# Power_Switching_Circuit_rev3.net
KiCad netlist of a schematic drawn in EAGLE
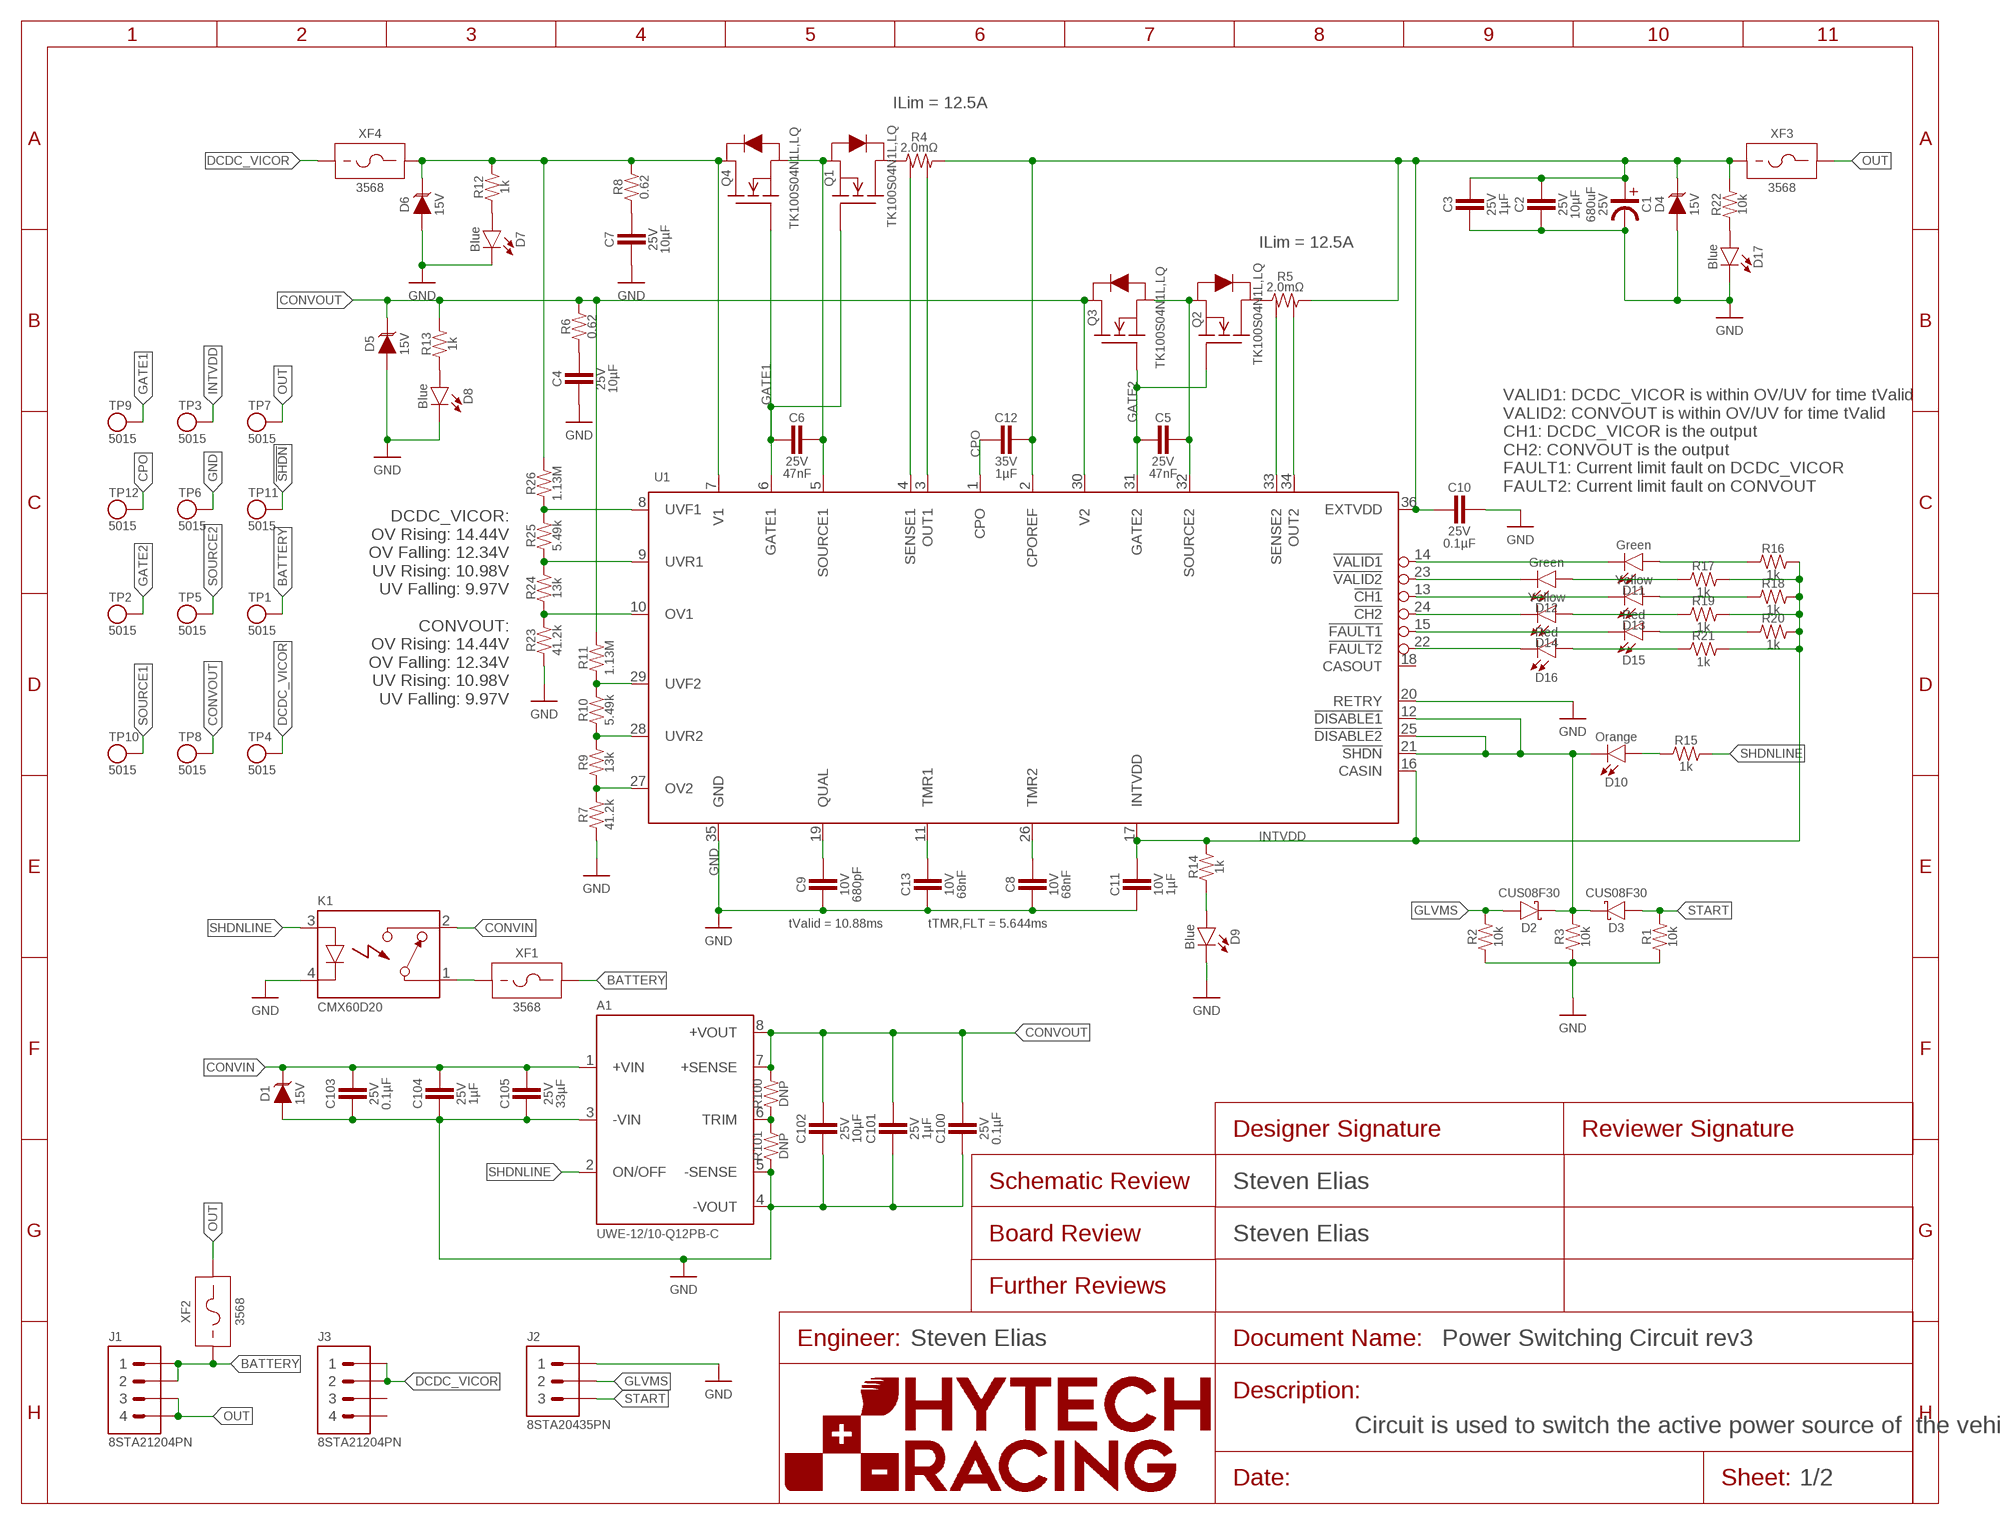
[diagram p0: schematic, sheet 1]
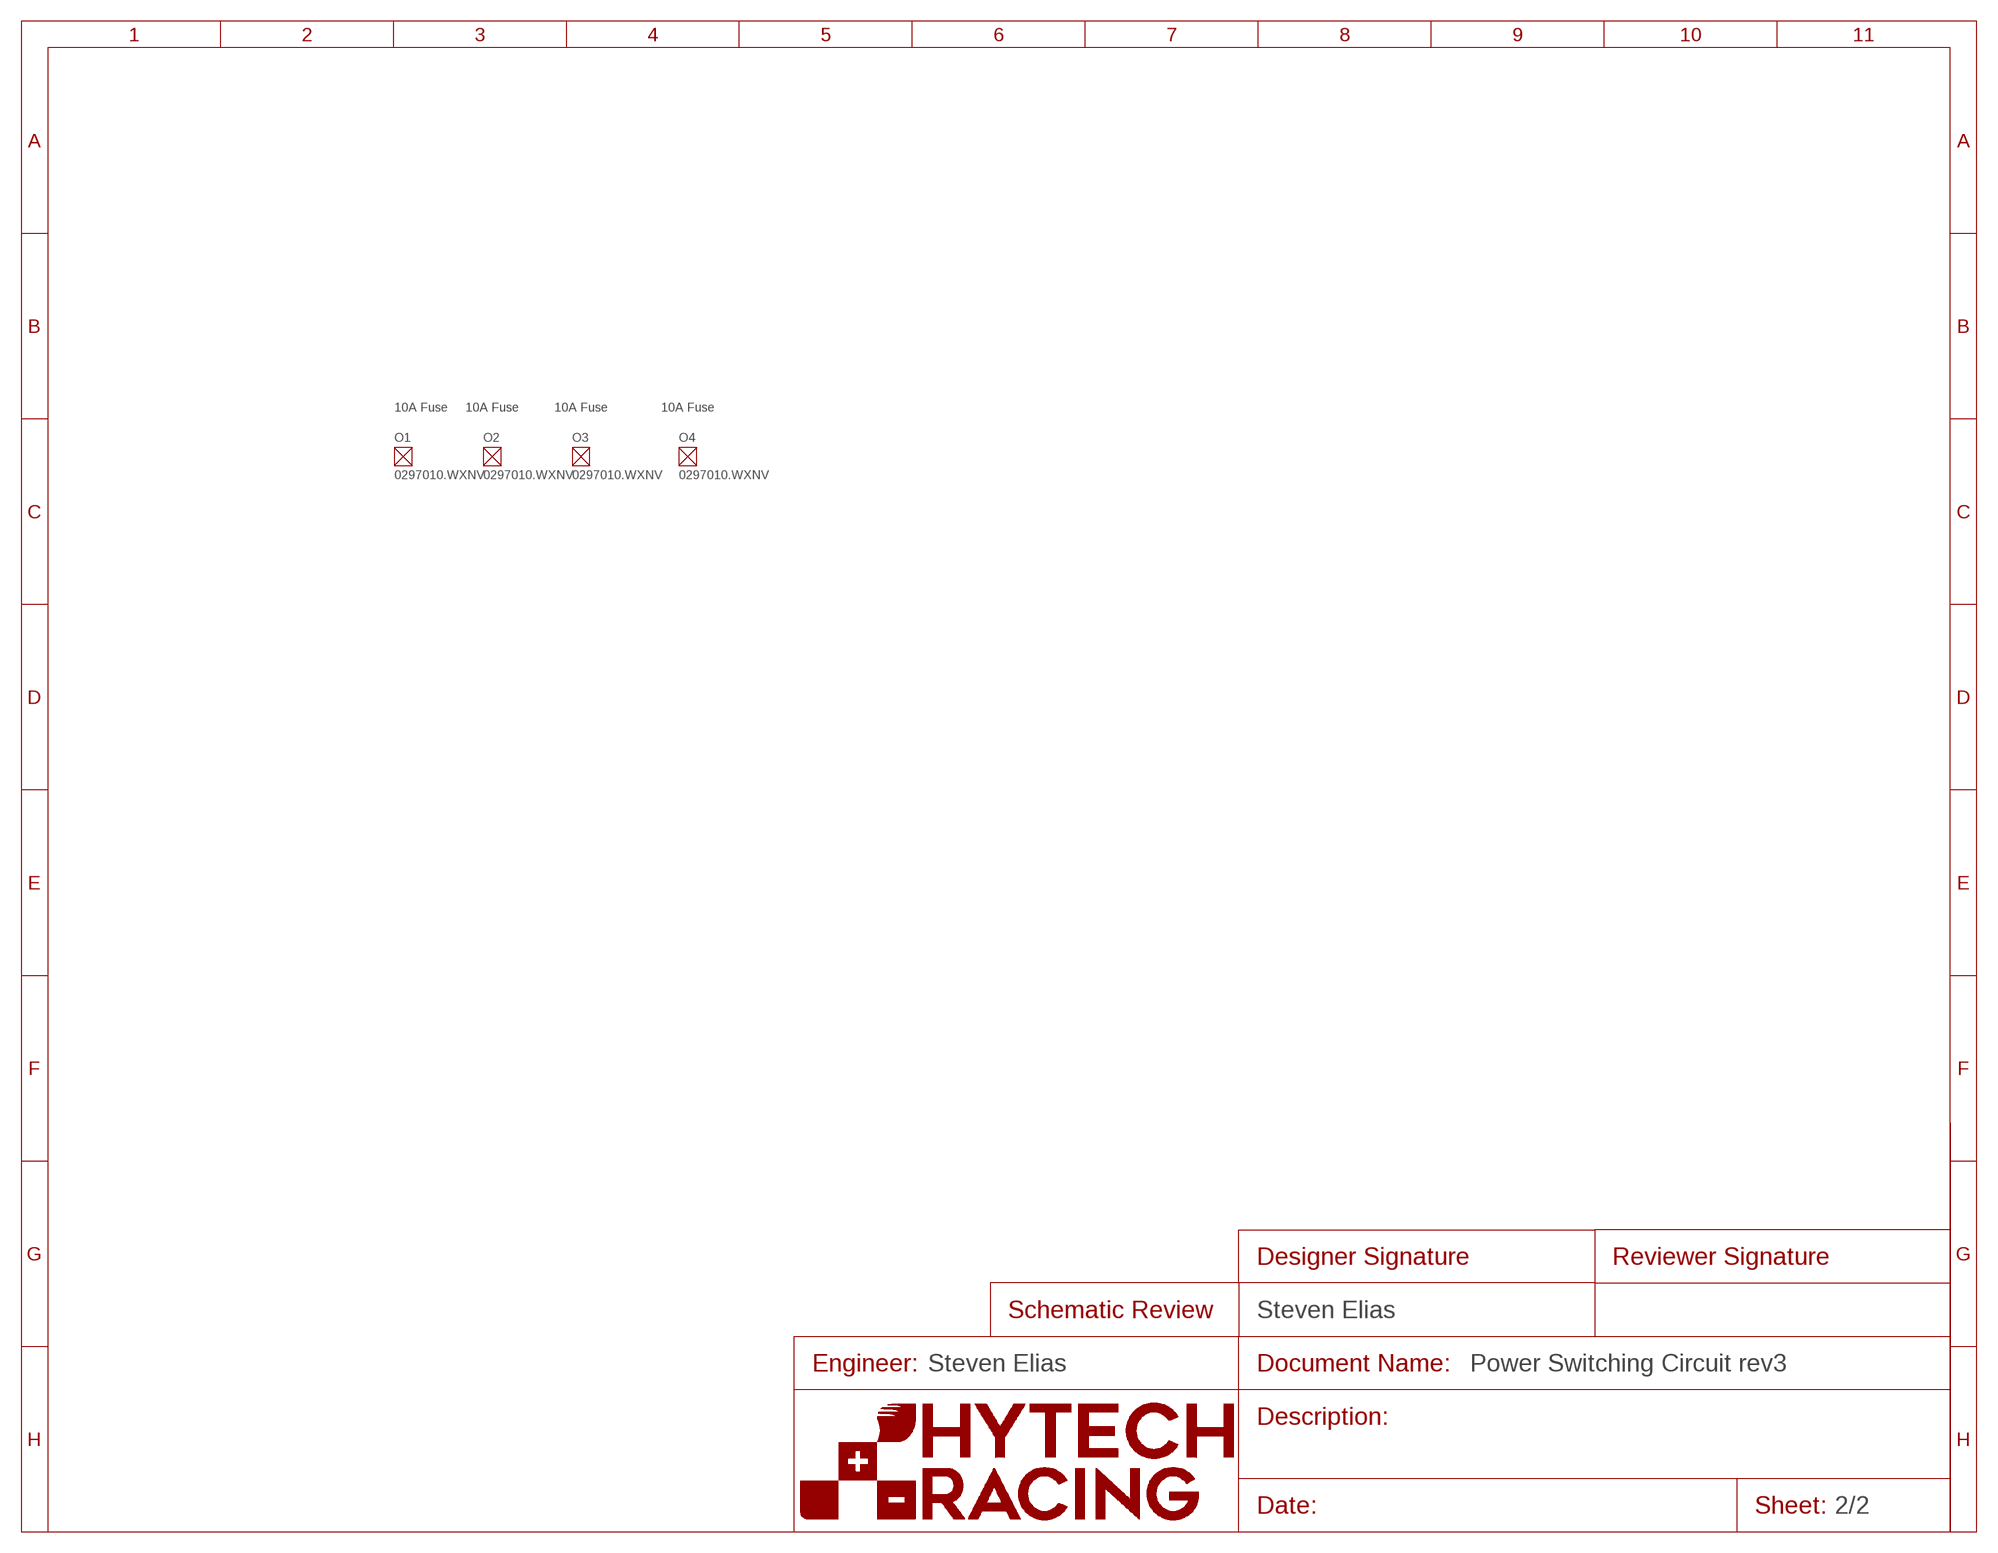
[diagram p1: schematic, sheet 2]

(export (version "E")
  (design (tool "Eeschema 10.0.6"))
  (components
    (comp (ref "A1")
      (value "UWE-12/10-Q12PB-C")
      (footprint "eagle-import:UWE-_")
      (fields
        (field (name "MANUFACTURER") "Murata Power Solutions Inc.")
        (field (name "MPN") "UWE-12/10-Q12PB-C")
      )
      (libsource (lib "eagle-import") (part "UWE-12/10-Q12PB-C"))
    )
    (comp (ref "C1")
      (value "EEUFP1E681")
      (footprint "eagle-import:EEUFP1E_")
      (fields
        (field (name "CAPACITANCE") "680uF")
        (field (name "MANUFACTURER") "Panasonic Electronic Components")
        (field (name "MPN") "EEU-FP1E681")
        (field (name "TOLERANCE") "20%")
        (field (name "VOLTAGE") "25V")
      )
      (libsource (lib "eagle-import") (part "EEUFP1E681"))
    )
    (comp (ref "C2")
      (value "CAPACITOR_0603_25V_10UF")
      (footprint "eagle-import:0603-CAP")
      (fields
        (field (name "CAPACITANCE") "10µF")
        (field (name "MANUFACTURER") "Murata Electronics")
        (field (name "MPN") "GRM188R61E106MA73D")
        (field (name "TOLERANCE") "20%")
        (field (name "VOLTAGE") "25V")
      )
      (libsource (lib "eagle-import") (part "CAPACITOR_?_060325V_10UF"))
    )
    (comp (ref "C3")
      (value "CAPACITOR_0603_25V_1UF")
      (footprint "eagle-import:0603-CAP")
      (fields
        (field (name "CAPACITANCE") "1µF")
        (field (name "MANUFACTURER") "Samsung Electro-Mechanics")
        (field (name "MPN") "CL10B105KA8NNNC")
        (field (name "TOLERANCE") "10%")
        (field (name "VOLTAGE") "25V")
      )
      (libsource (lib "eagle-import") (part "CAPACITOR_?_060325V_1UF"))
    )
    (comp (ref "C4")
      (value "CAPACITOR_0603_25V_10UF")
      (footprint "eagle-import:0603-CAP")
      (fields
        (field (name "CAPACITANCE") "10µF")
        (field (name "MANUFACTURER") "Murata Electronics")
        (field (name "MPN") "GRM188R61E106MA73D")
        (field (name "TOLERANCE") "20%")
        (field (name "VOLTAGE") "25V")
      )
      (libsource (lib "eagle-import") (part "CAPACITOR_?_060325V_10UF"))
    )
    (comp (ref "C5")
      (value "CAPACITOR_0603_25V_47NF")
      (footprint "eagle-import:0603-CAP")
      (fields
        (field (name "CAPACITANCE") "47nF")
        (field (name "MANUFACTURER") "Kyocera AVX")
        (field (name "MPN") "06033C473K4Z2A")
        (field (name "TOLERANCE") "10%")
        (field (name "VOLTAGE") "25V")
      )
      (libsource (lib "eagle-import") (part "CAPACITOR_?_060325V_47NF"))
    )
    (comp (ref "C6")
      (value "CAPACITOR_0603_25V_47NF")
      (footprint "eagle-import:0603-CAP")
      (fields
        (field (name "CAPACITANCE") "47nF")
        (field (name "MANUFACTURER") "Kyocera AVX")
        (field (name "MPN") "06033C473K4Z2A")
        (field (name "TOLERANCE") "10%")
        (field (name "VOLTAGE") "25V")
      )
      (libsource (lib "eagle-import") (part "CAPACITOR_?_060325V_47NF"))
    )
    (comp (ref "C7")
      (value "CAPACITOR_0603_25V_10UF")
      (footprint "eagle-import:0603-CAP")
      (fields
        (field (name "CAPACITANCE") "10µF")
        (field (name "MANUFACTURER") "Murata Electronics")
        (field (name "MPN") "GRM188R61E106MA73D")
        (field (name "TOLERANCE") "20%")
        (field (name "VOLTAGE") "25V")
      )
      (libsource (lib "eagle-import") (part "CAPACITOR_?_060325V_10UF"))
    )
    (comp (ref "C8")
      (value "CAPACITOR_0603_10V_68NF")
      (footprint "eagle-import:0603-CAP")
      (fields
        (field (name "CAPACITANCE") "68nF")
        (field (name "MANUFACTURER") "KEMET")
        (field (name "MPN") "C0603C683K8RACTU")
        (field (name "TOLERANCE") "10%")
        (field (name "VOLTAGE") "10V")
      )
      (libsource (lib "eagle-import") (part "CAPACITOR_?_060310V_68NF"))
    )
    (comp (ref "C9")
      (value "CAPACITOR_0603_10V_680PF")
      (footprint "eagle-import:0603-CAP")
      (fields
        (field (name "CAPACITANCE") "680pF")
        (field (name "MANUFACTURER") "Würth Elektronik")
        (field (name "MPN") "885012006013")
        (field (name "TOLERANCE") "5%")
        (field (name "VOLTAGE") "10V")
      )
      (libsource (lib "eagle-import") (part "CAPACITOR_?_060310V_680PF"))
    )
    (comp (ref "C10")
      (value "CAPACITOR_0603_25V_0.1UF")
      (footprint "eagle-import:0603-CAP")
      (fields
        (field (name "CAPACITANCE") "0.1µF")
        (field (name "MANUFACTURER") "Samsung Electro-Mechanics")
        (field (name "MPN") "CL10B104KA8NNNC")
        (field (name "TOLERANCE") "10%")
        (field (name "VOLTAGE") "25V")
      )
      (libsource (lib "eagle-import") (part "CAPACITOR_?_060325V_0.1UF"))
    )
    (comp (ref "C11")
      (value "CAPACITOR_0603_10V_1UF")
      (footprint "eagle-import:0603-CAP")
      (fields
        (field (name "CAPACITANCE") "1µF")
        (field (name "MANUFACTURER") "Yageo")
        (field (name "MPN") "CC0603KRX7R6BB105")
        (field (name "TOLERANCE") "10%")
        (field (name "VOLTAGE") "10V")
      )
      (libsource (lib "eagle-import") (part "CAPACITOR_?_060310V_1UF"))
    )
    (comp (ref "C12")
      (value "CAPACITOR_0603_35V_1UF")
      (footprint "eagle-import:0603-CAP")
      (fields
        (field (name "CAPACITANCE") "1µF")
        (field (name "MANUFACTURER") "TDK Corporation")
        (field (name "MPN") "C1608X7R1V105K080AE")
        (field (name "TOLERANCE") "10%")
        (field (name "VOLTAGE") "35V")
      )
      (libsource (lib "eagle-import") (part "CAPACITOR_?_060335V_1UF"))
    )
    (comp (ref "C13")
      (value "CAPACITOR_0603_10V_68NF")
      (footprint "eagle-import:0603-CAP")
      (fields
        (field (name "CAPACITANCE") "68nF")
        (field (name "MANUFACTURER") "KEMET")
        (field (name "MPN") "C0603C683K8RACTU")
        (field (name "TOLERANCE") "10%")
        (field (name "VOLTAGE") "10V")
      )
      (libsource (lib "eagle-import") (part "CAPACITOR_?_060310V_68NF"))
    )
    (comp (ref "C100")
      (value "CAPACITOR_0603_25V_0.1UF")
      (footprint "eagle-import:0603-CAP")
      (fields
        (field (name "CAPACITANCE") "0.1µF")
        (field (name "MANUFACTURER") "Samsung Electro-Mechanics")
        (field (name "MPN") "CL10B104KA8NNNC")
        (field (name "TOLERANCE") "10%")
        (field (name "VOLTAGE") "25V")
      )
      (libsource (lib "eagle-import") (part "CAPACITOR_?_060325V_0.1UF"))
    )
    (comp (ref "C101")
      (value "CAPACITOR_0603_25V_1UF")
      (footprint "eagle-import:0603-CAP")
      (fields
        (field (name "CAPACITANCE") "1µF")
        (field (name "MANUFACTURER") "Samsung Electro-Mechanics")
        (field (name "MPN") "CL10B105KA8NNNC")
        (field (name "TOLERANCE") "10%")
        (field (name "VOLTAGE") "25V")
      )
      (libsource (lib "eagle-import") (part "CAPACITOR_?_060325V_1UF"))
    )
    (comp (ref "C102")
      (value "CAPACITOR_0603_25V_10UF")
      (footprint "eagle-import:0603-CAP")
      (fields
        (field (name "CAPACITANCE") "10µF")
        (field (name "MANUFACTURER") "Murata Electronics")
        (field (name "MPN") "GRM188R61E106MA73D")
        (field (name "TOLERANCE") "20%")
        (field (name "VOLTAGE") "25V")
      )
      (libsource (lib "eagle-import") (part "CAPACITOR_?_060325V_10UF"))
    )
    (comp (ref "C103")
      (value "CAPACITOR_0603_25V_0.1UF")
      (footprint "eagle-import:0603-CAP")
      (fields
        (field (name "CAPACITANCE") "0.1µF")
        (field (name "MANUFACTURER") "Samsung Electro-Mechanics")
        (field (name "MPN") "CL10B104KA8NNNC")
        (field (name "TOLERANCE") "10%")
        (field (name "VOLTAGE") "25V")
      )
      (libsource (lib "eagle-import") (part "CAPACITOR_?_060325V_0.1UF"))
    )
    (comp (ref "C104")
      (value "CAPACITOR_0603_25V_1UF")
      (footprint "eagle-import:0603-CAP")
      (fields
        (field (name "CAPACITANCE") "1µF")
        (field (name "MANUFACTURER") "Samsung Electro-Mechanics")
        (field (name "MPN") "CL10B105KA8NNNC")
        (field (name "TOLERANCE") "10%")
        (field (name "VOLTAGE") "25V")
      )
      (libsource (lib "eagle-import") (part "CAPACITOR_?_060325V_1UF"))
    )
    (comp (ref "C105")
      (value "CAPACITOR_1206_25V_33UF")
      (footprint "eagle-import:1206-CAP")
      (fields
        (field (name "CAPACITANCE") "33µF")
        (field (name "MANUFACTURER") "TDK Corporation")
        (field (name "MPN") "C3216X5R1E336M160AC")
        (field (name "TOLERANCE") "20%")
        (field (name "VOLTAGE") "25V")
      )
      (libsource (lib "eagle-import") (part "CAPACITOR_?_120625V_33UF"))
    )
    (comp (ref "D1")
      (value "TVS_15V")
      (footprint "eagle-import:SOT-23")
      (fields
        (field (name "MANUFACTURER") "Vishay General Semiconductor - Diodes Division")
        (field (name "MPN") "GSOT15-E3-08")
        (field (name "VOLTAGE") "15V")
      )
      (libsource (lib "eagle-import") (part "TVS_15V"))
    )
    (comp (ref "D2")
      (value "SCHOTTKY_SOD323_30V")
      (footprint "eagle-import:SOD-323")
      (fields
        (field (name "MANUFACTURER") "Toshiba Semiconductor and Storage")
        (field (name "MPN") "CUS08F30")
        (field (name "VOLTAGE") "30V")
      )
      (libsource (lib "eagle-import") (part "SCHOTTKY_?_SOD32330V"))
    )
    (comp (ref "D3")
      (value "SCHOTTKY_SOD323_30V")
      (footprint "eagle-import:SOD-323")
      (fields
        (field (name "MANUFACTURER") "Toshiba Semiconductor and Storage")
        (field (name "MPN") "CUS08F30")
        (field (name "VOLTAGE") "30V")
      )
      (libsource (lib "eagle-import") (part "SCHOTTKY_?_SOD32330V"))
    )
    (comp (ref "D4")
      (value "TVS_15V")
      (footprint "eagle-import:SOT-23")
      (fields
        (field (name "MANUFACTURER") "Vishay General Semiconductor - Diodes Division")
        (field (name "MPN") "GSOT15-E3-08")
        (field (name "VOLTAGE") "15V")
      )
      (libsource (lib "eagle-import") (part "TVS_15V"))
    )
    (comp (ref "D5")
      (value "TVS_15V")
      (footprint "eagle-import:SOT-23")
      (fields
        (field (name "MANUFACTURER") "Vishay General Semiconductor - Diodes Division")
        (field (name "MPN") "GSOT15-E3-08")
        (field (name "VOLTAGE") "15V")
      )
      (libsource (lib "eagle-import") (part "TVS_15V"))
    )
    (comp (ref "D6")
      (value "TVS_15V")
      (footprint "eagle-import:SOT-23")
      (fields
        (field (name "MANUFACTURER") "Vishay General Semiconductor - Diodes Division")
        (field (name "MPN") "GSOT15-E3-08")
        (field (name "VOLTAGE") "15V")
      )
      (libsource (lib "eagle-import") (part "TVS_15V"))
    )
    (comp (ref "D7")
      (value "LED_0603_BLUE")
      (footprint "eagle-import:0603-LED")
      (fields
        (field (name "COLOR") "Blue")
        (field (name "MANUFACTURER") "Kingbright")
        (field (name "MPN") "APT1608VBC/D")
      )
      (libsource (lib "eagle-import") (part "LED_?_0603BLUE"))
    )
    (comp (ref "D8")
      (value "LED_0603_BLUE")
      (footprint "eagle-import:0603-LED")
      (fields
        (field (name "COLOR") "Blue")
        (field (name "MANUFACTURER") "Kingbright")
        (field (name "MPN") "APT1608VBC/D")
      )
      (libsource (lib "eagle-import") (part "LED_?_0603BLUE"))
    )
    (comp (ref "D9")
      (value "LED_0603_BLUE")
      (footprint "eagle-import:0603-LED")
      (fields
        (field (name "COLOR") "Blue")
        (field (name "MANUFACTURER") "Kingbright")
        (field (name "MPN") "APT1608VBC/D")
      )
      (libsource (lib "eagle-import") (part "LED_?_0603BLUE"))
    )
    (comp (ref "D10")
      (value "LED_0603_ORANGE")
      (footprint "eagle-import:0603-LED")
      (fields
        (field (name "COLOR") "Orange")
        (field (name "MANUFACTURER") "Kingbright")
        (field (name "MPN") "APT1608SECK")
      )
      (libsource (lib "eagle-import") (part "LED_?_0603ORANGE"))
    )
    (comp (ref "D11")
      (value "LED_0603_GREEN")
      (footprint "eagle-import:0603-LED")
      (fields
        (field (name "COLOR") "Green")
        (field (name "MANUFACTURER") "Kingbright")
        (field (name "MPN") "APT1608ZGCK")
      )
      (libsource (lib "eagle-import") (part "LED_?_0603GREEN"))
    )
    (comp (ref "D12")
      (value "LED_0603_GREEN")
      (footprint "eagle-import:0603-LED")
      (fields
        (field (name "COLOR") "Green")
        (field (name "MANUFACTURER") "Kingbright")
        (field (name "MPN") "APT1608ZGCK")
      )
      (libsource (lib "eagle-import") (part "LED_?_0603GREEN"))
    )
    (comp (ref "D13")
      (value "LED_0603_YELLOW")
      (footprint "eagle-import:0603-LED")
      (fields
        (field (name "COLOR") "Yellow")
        (field (name "MANUFACTURER") "Kingbright")
        (field (name "MPN") "APT1608SYCK/J3-PRV")
      )
      (libsource (lib "eagle-import") (part "LED_?_0603YELLOW"))
    )
    (comp (ref "D14")
      (value "LED_0603_YELLOW")
      (footprint "eagle-import:0603-LED")
      (fields
        (field (name "COLOR") "Yellow")
        (field (name "MANUFACTURER") "Kingbright")
        (field (name "MPN") "APT1608SYCK/J3-PRV")
      )
      (libsource (lib "eagle-import") (part "LED_?_0603YELLOW"))
    )
    (comp (ref "D15")
      (value "LED_0603_RED")
      (footprint "eagle-import:0603-LED")
      (fields
        (field (name "COLOR") "Red")
        (field (name "MANUFACTURER") "Kingbright")
        (field (name "MPN") "APT1608SECK/J3-PRV")
      )
      (libsource (lib "eagle-import") (part "LED_?_0603RED"))
    )
    (comp (ref "D16")
      (value "LED_0603_RED")
      (footprint "eagle-import:0603-LED")
      (fields
        (field (name "COLOR") "Red")
        (field (name "MANUFACTURER") "Kingbright")
        (field (name "MPN") "APT1608SECK/J3-PRV")
      )
      (libsource (lib "eagle-import") (part "LED_?_0603RED"))
    )
    (comp (ref "D17")
      (value "LED_0603_BLUE")
      (footprint "eagle-import:0603-LED")
      (fields
        (field (name "COLOR") "Blue")
        (field (name "MANUFACTURER") "Kingbright")
        (field (name "MPN") "APT1608VBC/D")
      )
      (libsource (lib "eagle-import") (part "LED_?_0603BLUE"))
    )
    (comp (ref "J1")
      (value "CONNECTOR-4_SOURIAU_")
      (footprint "eagle-import:SOURIAU_12-04")
      (fields (field (name "MPN") "8STA21204PN") (field (name "MANUFACTURER") "Souriau"))
      (libsource (lib "eagle-import") (part "CONNECTOR-4_?_SOURIAU"))
    )
    (comp (ref "J2")
      (value "CONNECTOR-3_8STA20435PN")
      (footprint "eagle-import:SOURIAU_04-35")
      (fields (field (name "MANUFACTURER") "Souriau") (field (name "MPN") "8STA20435PN"))
      (libsource (lib "eagle-import") (part "CONNECTOR-3_?8STA20435PN"))
    )
    (comp (ref "J3")
      (value "CONNECTOR-4_SOURIAU_")
      (footprint "eagle-import:SOURIAU_12-04")
      (fields (field (name "MPN") "8STA21204PN") (field (name "MANUFACTURER") "Souriau"))
      (libsource (lib "eagle-import") (part "CONNECTOR-4_?_SOURIAU"))
    )
    (comp (ref "K1")
      (value "RELAY_SOLIDSTATE_NO_CMX60D20")
      (footprint "eagle-import:CRYDOM_CMX")
      (fields (field (name "MANUFACTURER") "Crydom") (field (name "MPN") "CMX60D20"))
      (libsource (lib "eagle-import") (part "RELAY_SOLIDSTATE_NO_?CMX60D20"))
    )
    (comp (ref "Q1")
      (value "TRANSISTOR_N_MOS_2-7K1S_TK100S04N1LLQ")
      (footprint "eagle-import:DPAK(2-7K1S)")
      (fields
        (field (name "MANUFACTURER") "Toshiba Semiconductor and Storage")
        (field (name "MPN") "TK100S04N1L,LQ")
      )
      (libsource (lib "eagle-import") (part "TRANSISTOR_N_MOS_?_2-7K1STK100S04N1LLQ"))
    )
    (comp (ref "Q2")
      (value "TRANSISTOR_N_MOS_2-7K1S_TK100S04N1LLQ")
      (footprint "eagle-import:DPAK(2-7K1S)")
      (fields
        (field (name "MANUFACTURER") "Toshiba Semiconductor and Storage")
        (field (name "MPN") "TK100S04N1L,LQ")
      )
      (libsource (lib "eagle-import") (part "TRANSISTOR_N_MOS_?_2-7K1STK100S04N1LLQ"))
    )
    (comp (ref "Q3")
      (value "TRANSISTOR_N_MOS_2-7K1S_TK100S04N1LLQ")
      (footprint "eagle-import:DPAK(2-7K1S)")
      (fields
        (field (name "MANUFACTURER") "Toshiba Semiconductor and Storage")
        (field (name "MPN") "TK100S04N1L,LQ")
      )
      (libsource (lib "eagle-import") (part "TRANSISTOR_N_MOS_?_2-7K1STK100S04N1LLQ"))
    )
    (comp (ref "Q4")
      (value "TRANSISTOR_N_MOS_2-7K1S_TK100S04N1LLQ")
      (footprint "eagle-import:DPAK(2-7K1S)")
      (fields
        (field (name "MANUFACTURER") "Toshiba Semiconductor and Storage")
        (field (name "MPN") "TK100S04N1L,LQ")
      )
      (libsource (lib "eagle-import") (part "TRANSISTOR_N_MOS_?_2-7K1STK100S04N1LLQ"))
    )
    (comp (ref "R1")
      (value "RESISTOR_0603_10K")
      (footprint "eagle-import:0603-RES")
      (fields
        (field (name "MANUFACTURER") "Yageo")
        (field (name "MPN") "RC0603FR-0710KL")
        (field (name "POWER") "0.1W")
        (field (name "RESISTANCE") "10k")
      )
      (libsource (lib "eagle-import") (part "RESISTOR_?_060310K"))
    )
    (comp (ref "R2")
      (value "RESISTOR_0603_10K")
      (footprint "eagle-import:0603-RES")
      (fields
        (field (name "MANUFACTURER") "Yageo")
        (field (name "MPN") "RC0603FR-0710KL")
        (field (name "POWER") "0.1W")
        (field (name "RESISTANCE") "10k")
      )
      (libsource (lib "eagle-import") (part "RESISTOR_?_060310K"))
    )
    (comp (ref "R3")
      (value "RESISTOR_0603_10K")
      (footprint "eagle-import:0603-RES")
      (fields
        (field (name "MANUFACTURER") "Yageo")
        (field (name "MPN") "RC0603FR-0710KL")
        (field (name "POWER") "0.1W")
        (field (name "RESISTANCE") "10k")
      )
      (libsource (lib "eagle-import") (part "RESISTOR_?_060310K"))
    )
    (comp (ref "R4")
      (value "RESISTOR_SENSE__WSL40262L000FEB")
      (footprint "eagle-import:4026")
      (fields
        (field (name "MANUFACTURER") "Vishay Dale")
        (field (name "MPN") "WSL40262L000FEB")
        (field (name "POWER") "3W")
        (field (name "RESISTANCE") "2.0mΩ")
      )
      (libsource (lib "eagle-import") (part "RESISTOR_SENSE_?_WSL40262L000FEB"))
    )
    (comp (ref "R5")
      (value "RESISTOR_SENSE__WSL40262L000FEB")
      (footprint "eagle-import:4026")
      (fields
        (field (name "MANUFACTURER") "Vishay Dale")
        (field (name "MPN") "WSL40262L000FEB")
        (field (name "POWER") "3W")
        (field (name "RESISTANCE") "2.0mΩ")
      )
      (libsource (lib "eagle-import") (part "RESISTOR_SENSE_?_WSL40262L000FEB"))
    )
    (comp (ref "R6")
      (value "RESISTOR_0805_0.62")
      (footprint "eagle-import:0805-RES")
      (fields
        (field (name "MANUFACTURER") "Yageo")
        (field (name "MPN") "RL0805FR-070R62L")
        (field (name "POWER") "0.125W")
        (field (name "RESISTANCE") "0.62")
      )
      (libsource (lib "eagle-import") (part "RESISTOR_?_08050.62"))
    )
    (comp (ref "R7")
      (value "RESISTOR_0603_41.2K")
      (footprint "eagle-import:0603-RES")
      (fields
        (field (name "MANUFACTURER") "Panasonic Electronic Components")
        (field (name "MPN") " ERJ-PB3B4122V")
        (field (name "POWER") "0.2W")
        (field (name "RESISTANCE") "41.2k")
      )
      (libsource (lib "eagle-import") (part "RESISTOR_?_060341.2K"))
    )
    (comp (ref "R8")
      (value "RESISTOR_0805_0.62")
      (footprint "eagle-import:0805-RES")
      (fields
        (field (name "MANUFACTURER") "Yageo")
        (field (name "MPN") "RL0805FR-070R62L")
        (field (name "POWER") "0.125W")
        (field (name "RESISTANCE") "0.62")
      )
      (libsource (lib "eagle-import") (part "RESISTOR_?_08050.62"))
    )
    (comp (ref "R9")
      (value "RESISTOR_0603_13K")
      (footprint "eagle-import:0603-RES")
      (fields
        (field (name "MANUFACTURER") "Panasonic Electronic Components")
        (field (name "MPN") "ERA-3ARW133V")
        (field (name "POWER") "0.1W")
        (field (name "RESISTANCE") "13k")
      )
      (libsource (lib "eagle-import") (part "RESISTOR_?_060313K"))
    )
    (comp (ref "R10")
      (value "RESISTOR_0603_5.49K")
      (footprint "eagle-import:0603-RES")
      (fields
        (field (name "MANUFACTURER") "Panasonic Electronic Components")
        (field (name "MPN") "ERJ-PB3D5491V")
        (field (name "POWER") "0.2W")
        (field (name "RESISTANCE") "5.49k")
      )
      (libsource (lib "eagle-import") (part "RESISTOR_?_06035.49K"))
    )
    (comp (ref "R11")
      (value "RESISTOR_0603_1.13M")
      (footprint "eagle-import:0603-RES")
      (fields
        (field (name "MANUFACTURER") "Vishay Dale")
        (field (name "MPN") "CRCW06031M13FKEA")
        (field (name "POWER") "0.1W")
        (field (name "RESISTANCE") "1.13M")
      )
      (libsource (lib "eagle-import") (part "RESISTOR_?_06031.13M"))
    )
    (comp (ref "R12")
      (value "RESISTOR_0603_1K")
      (footprint "eagle-import:0603-RES")
      (fields
        (field (name "MANUFACTURER") "Yageo")
        (field (name "MPN") "RC0603FR-071KL")
        (field (name "POWER") "0.1W")
        (field (name "RESISTANCE") "1k")
      )
      (libsource (lib "eagle-import") (part "RESISTOR_?_06031K"))
    )
    (comp (ref "R13")
      (value "RESISTOR_0603_1K")
      (footprint "eagle-import:0603-RES")
      (fields
        (field (name "MANUFACTURER") "Yageo")
        (field (name "MPN") "RC0603FR-071KL")
        (field (name "POWER") "0.1W")
        (field (name "RESISTANCE") "1k")
      )
      (libsource (lib "eagle-import") (part "RESISTOR_?_06031K"))
    )
    (comp (ref "R14")
      (value "RESISTOR_0603_1K")
      (footprint "eagle-import:0603-RES")
      (fields
        (field (name "MANUFACTURER") "Yageo")
        (field (name "MPN") "RC0603FR-071KL")
        (field (name "POWER") "0.1W")
        (field (name "RESISTANCE") "1k")
      )
      (libsource (lib "eagle-import") (part "RESISTOR_?_06031K"))
    )
    (comp (ref "R15")
      (value "RESISTOR_0603_1K")
      (footprint "eagle-import:0603-RES")
      (fields
        (field (name "MANUFACTURER") "Yageo")
        (field (name "MPN") "RC0603FR-071KL")
        (field (name "POWER") "0.1W")
        (field (name "RESISTANCE") "1k")
      )
      (libsource (lib "eagle-import") (part "RESISTOR_?_06031K"))
    )
    (comp (ref "R16")
      (value "RESISTOR_0603_1K")
      (footprint "eagle-import:0603-RES")
      (fields
        (field (name "MANUFACTURER") "Yageo")
        (field (name "MPN") "RC0603FR-071KL")
        (field (name "POWER") "0.1W")
        (field (name "RESISTANCE") "1k")
      )
      (libsource (lib "eagle-import") (part "RESISTOR_?_06031K"))
    )
    (comp (ref "R17")
      (value "RESISTOR_0603_1K")
      (footprint "eagle-import:0603-RES")
      (fields
        (field (name "MANUFACTURER") "Yageo")
        (field (name "MPN") "RC0603FR-071KL")
        (field (name "POWER") "0.1W")
        (field (name "RESISTANCE") "1k")
      )
      (libsource (lib "eagle-import") (part "RESISTOR_?_06031K"))
    )
    (comp (ref "R18")
      (value "RESISTOR_0603_1K")
      (footprint "eagle-import:0603-RES")
      (fields
        (field (name "MANUFACTURER") "Yageo")
        (field (name "MPN") "RC0603FR-071KL")
        (field (name "POWER") "0.1W")
        (field (name "RESISTANCE") "1k")
      )
      (libsource (lib "eagle-import") (part "RESISTOR_?_06031K"))
    )
    (comp (ref "R19")
      (value "RESISTOR_0603_1K")
      (footprint "eagle-import:0603-RES")
      (fields
        (field (name "MANUFACTURER") "Yageo")
        (field (name "MPN") "RC0603FR-071KL")
        (field (name "POWER") "0.1W")
        (field (name "RESISTANCE") "1k")
      )
      (libsource (lib "eagle-import") (part "RESISTOR_?_06031K"))
    )
    (comp (ref "R20")
      (value "RESISTOR_0603_1K")
      (footprint "eagle-import:0603-RES")
      (fields
        (field (name "MANUFACTURER") "Yageo")
        (field (name "MPN") "RC0603FR-071KL")
        (field (name "POWER") "0.1W")
        (field (name "RESISTANCE") "1k")
      )
      (libsource (lib "eagle-import") (part "RESISTOR_?_06031K"))
    )
    (comp (ref "R21")
      (value "RESISTOR_0603_1K")
      (footprint "eagle-import:0603-RES")
      (fields
        (field (name "MANUFACTURER") "Yageo")
        (field (name "MPN") "RC0603FR-071KL")
        (field (name "POWER") "0.1W")
        (field (name "RESISTANCE") "1k")
      )
      (libsource (lib "eagle-import") (part "RESISTOR_?_06031K"))
    )
    (comp (ref "R22")
      (value "RESISTOR_0603_10K")
      (footprint "eagle-import:0603-RES")
      (fields
        (field (name "MANUFACTURER") "Yageo")
        (field (name "MPN") "RC0603FR-0710KL")
        (field (name "POWER") "0.1W")
        (field (name "RESISTANCE") "10k")
      )
      (libsource (lib "eagle-import") (part "RESISTOR_?_060310K"))
    )
    (comp (ref "R23")
      (value "RESISTOR_0603_41.2K")
      (footprint "eagle-import:0603-RES")
      (fields
        (field (name "MANUFACTURER") "Panasonic Electronic Components")
        (field (name "MPN") " ERJ-PB3B4122V")
        (field (name "POWER") "0.2W")
        (field (name "RESISTANCE") "41.2k")
      )
      (libsource (lib "eagle-import") (part "RESISTOR_?_060341.2K"))
    )
    (comp (ref "R24")
      (value "RESISTOR_0603_13K")
      (footprint "eagle-import:0603-RES")
      (fields
        (field (name "MANUFACTURER") "Panasonic Electronic Components")
        (field (name "MPN") "ERA-3ARW133V")
        (field (name "POWER") "0.1W")
        (field (name "RESISTANCE") "13k")
      )
      (libsource (lib "eagle-import") (part "RESISTOR_?_060313K"))
    )
    (comp (ref "R25")
      (value "RESISTOR_0603_5.49K")
      (footprint "eagle-import:0603-RES")
      (fields
        (field (name "MANUFACTURER") "Panasonic Electronic Components")
        (field (name "MPN") "ERJ-PB3D5491V")
        (field (name "POWER") "0.2W")
        (field (name "RESISTANCE") "5.49k")
      )
      (libsource (lib "eagle-import") (part "RESISTOR_?_06035.49K"))
    )
    (comp (ref "R26")
      (value "RESISTOR_0603_1.13M")
      (footprint "eagle-import:0603-RES")
      (fields
        (field (name "MANUFACTURER") "Vishay Dale")
        (field (name "MPN") "CRCW06031M13FKEA")
        (field (name "POWER") "0.1W")
        (field (name "RESISTANCE") "1.13M")
      )
      (libsource (lib "eagle-import") (part "RESISTOR_?_06031.13M"))
    )
    (comp (ref "R100")
      (value "RESISTOR_0603_DNP")
      (footprint "eagle-import:0603-RES")
      (fields (field (name "RESISTANCE") "DNP"))
      (libsource (lib "eagle-import") (part "RESISTOR_?_0603DNP"))
    )
    (comp (ref "R101")
      (value "RESISTOR_0603_DNP")
      (footprint "eagle-import:0603-RES")
      (fields (field (name "RESISTANCE") "DNP"))
      (libsource (lib "eagle-import") (part "RESISTOR_?_0603DNP"))
    )
    (comp (ref "TP1")
      (value "TEST_POINT")
      (footprint "eagle-import:5015")
      (fields (field (name "MPN") "5015") (field (name "MANUFACTURER") "Keystone Electronics"))
      (libsource (lib "eagle-import") (part "TEST_POINT"))
    )
    (comp (ref "TP2")
      (value "TEST_POINT")
      (footprint "eagle-import:5015")
      (fields (field (name "MPN") "5015") (field (name "MANUFACTURER") "Keystone Electronics"))
      (libsource (lib "eagle-import") (part "TEST_POINT"))
    )
    (comp (ref "TP3")
      (value "TEST_POINT")
      (footprint "eagle-import:5015")
      (fields (field (name "MPN") "5015") (field (name "MANUFACTURER") "Keystone Electronics"))
      (libsource (lib "eagle-import") (part "TEST_POINT"))
    )
    (comp (ref "TP4")
      (value "TEST_POINT")
      (footprint "eagle-import:5015")
      (fields (field (name "MPN") "5015") (field (name "MANUFACTURER") "Keystone Electronics"))
      (libsource (lib "eagle-import") (part "TEST_POINT"))
    )
    (comp (ref "TP5")
      (value "TEST_POINT")
      (footprint "eagle-import:5015")
      (fields (field (name "MPN") "5015") (field (name "MANUFACTURER") "Keystone Electronics"))
      (libsource (lib "eagle-import") (part "TEST_POINT"))
    )
    (comp (ref "TP6")
      (value "TEST_POINT")
      (footprint "eagle-import:5015")
      (fields (field (name "MPN") "5015") (field (name "MANUFACTURER") "Keystone Electronics"))
      (libsource (lib "eagle-import") (part "TEST_POINT"))
    )
    (comp (ref "TP7")
      (value "TEST_POINT")
      (footprint "eagle-import:5015")
      (fields (field (name "MPN") "5015") (field (name "MANUFACTURER") "Keystone Electronics"))
      (libsource (lib "eagle-import") (part "TEST_POINT"))
    )
    (comp (ref "TP8")
      (value "TEST_POINT")
      (footprint "eagle-import:5015")
      (fields (field (name "MPN") "5015") (field (name "MANUFACTURER") "Keystone Electronics"))
      (libsource (lib "eagle-import") (part "TEST_POINT"))
    )
    (comp (ref "TP9")
      (value "TEST_POINT")
      (footprint "eagle-import:5015")
      (fields (field (name "MPN") "5015") (field (name "MANUFACTURER") "Keystone Electronics"))
      (libsource (lib "eagle-import") (part "TEST_POINT"))
    )
    (comp (ref "TP10")
      (value "TEST_POINT")
      (footprint "eagle-import:5015")
      (fields (field (name "MPN") "5015") (field (name "MANUFACTURER") "Keystone Electronics"))
      (libsource (lib "eagle-import") (part "TEST_POINT"))
    )
    (comp (ref "TP11")
      (value "TEST_POINT")
      (footprint "eagle-import:5015")
      (fields (field (name "MPN") "5015") (field (name "MANUFACTURER") "Keystone Electronics"))
      (libsource (lib "eagle-import") (part "TEST_POINT"))
    )
    (comp (ref "TP12")
      (value "TEST_POINT")
      (footprint "eagle-import:5015")
      (fields (field (name "MPN") "5015") (field (name "MANUFACTURER") "Keystone Electronics"))
      (libsource (lib "eagle-import") (part "TEST_POINT"))
    )
    (comp (ref "U1")
      (value "LTC4421")
      (footprint "eagle-import:SSOP-36")
      (fields (field (name "MPN") "LTC4421CG#PBF") (field (name "MANUFACTURER") "Analog Devices Inc."))
      (libsource (lib "eagle-import") (part "LTC4421"))
    )
    (comp (ref "XF1")
      (value "FUSE_HOLDER_MINIBLADEPTH")
      (footprint "eagle-import:3568")
      (fields (field (name "MANUFACTURER") "Keystone") (field (name "MPN") "3568"))
      (libsource (lib "eagle-import") (part "FUSE_HOLDER_PTHMINIBLADE"))
    )
    (comp (ref "XF2")
      (value "FUSE_HOLDER_MINIBLADEPTH")
      (footprint "eagle-import:3568")
      (fields (field (name "MANUFACTURER") "Keystone") (field (name "MPN") "3568"))
      (libsource (lib "eagle-import") (part "FUSE_HOLDER_PTHMINIBLADE"))
    )
    (comp (ref "XF3")
      (value "FUSE_HOLDER_MINIBLADEPTH")
      (footprint "eagle-import:3568")
      (fields (field (name "MANUFACTURER") "Keystone") (field (name "MPN") "3568"))
      (libsource (lib "eagle-import") (part "FUSE_HOLDER_PTHMINIBLADE"))
    )
    (comp (ref "XF4")
      (value "FUSE_HOLDER_MINIBLADEPTH")
      (footprint "eagle-import:3568")
      (fields (field (name "MANUFACTURER") "Keystone") (field (name "MPN") "3568"))
      (libsource (lib "eagle-import") (part "FUSE_HOLDER_PTHMINIBLADE"))
    )
  )
  (nets
    (net (code "1") (name "BATTERY") (class "Default")
      (node (ref "J1") (pin "1") (pinfunction "1_1") (pintype "passive"))
      (node (ref "J1") (pin "2") (pinfunction "2_2") (pintype "passive"))
      (node (ref "TP1") (pin "1") (pinfunction "1_1") (pintype "passive"))
      (node (ref "XF1") (pin "3") (pinfunction "2_3") (pintype "passive"))
      (node (ref "XF1") (pin "4") (pinfunction "2_4") (pintype "passive"))
      (node (ref "XF2") (pin "1") (pinfunction "1_1") (pintype "passive"))
      (node (ref "XF2") (pin "2") (pinfunction "1_2") (pintype "passive"))
    )
    (net (code "2") (name "CONVIN") (class "Default")
      (node (ref "A1") (pin "1") (pinfunction "+VIN_1") (pintype "input"))
      (node (ref "C103") (pin "1") (pinfunction "1_1") (pintype "passive"))
      (node (ref "C104") (pin "1") (pinfunction "1_1") (pintype "passive"))
      (node (ref "C105") (pin "1") (pinfunction "1_1") (pintype "passive"))
      (node (ref "D1") (pin "3") (pinfunction "C_3") (pintype "passive"))
      (node (ref "K1") (pin "2") (pinfunction "CONTACT2_2") (pintype "bidirectional"))
    )
    (net (code "3") (name "CONVOUT") (class "Default")
      (node (ref "A1") (pin "7") (pinfunction "+SENSE_7") (pintype "input"))
      (node (ref "A1") (pin "8") (pinfunction "+VOUT_8") (pintype "power_in"))
      (node (ref "C100") (pin "1") (pinfunction "1_1") (pintype "passive"))
      (node (ref "C101") (pin "1") (pinfunction "1_1") (pintype "passive"))
      (node (ref "C102") (pin "1") (pinfunction "1_1") (pintype "passive"))
      (node (ref "D5") (pin "3") (pinfunction "C_3") (pintype "passive"))
      (node (ref "Q3") (pin "2") (pinfunction "D_2") (pintype "passive"))
      (node (ref "R100") (pin "2") (pinfunction "2_2") (pintype "passive"))
      (node (ref "R11") (pin "2") (pinfunction "2_2") (pintype "passive"))
      (node (ref "R13") (pin "2") (pinfunction "2_2") (pintype "passive"))
      (node (ref "R6") (pin "2") (pinfunction "2_2") (pintype "passive"))
      (node (ref "TP8") (pin "1") (pinfunction "1_1") (pintype "passive"))
      (node (ref "U1") (pin "30") (pinfunction "V2_30") (pintype "input"))
    )
    (net (code "4") (name "CPO") (class "Default")
      (node (ref "C12") (pin "2") (pinfunction "2_2") (pintype "passive"))
      (node (ref "TP12") (pin "1") (pinfunction "1_1") (pintype "passive"))
      (node (ref "U1") (pin "1") (pinfunction "CPO_1") (pintype "input"))
    )
    (net (code "5") (name "DCDC_VICOR") (class "Default")
      (node (ref "J3") (pin "1") (pinfunction "1_1") (pintype "passive"))
      (node (ref "J3") (pin "2") (pinfunction "2_2") (pintype "passive"))
      (node (ref "TP4") (pin "1") (pinfunction "1_1") (pintype "passive"))
      (node (ref "XF4") (pin "1") (pinfunction "1_1") (pintype "passive"))
      (node (ref "XF4") (pin "2") (pinfunction "1_2") (pintype "passive"))
    )
    (net (code "6") (name "GATE1") (class "Default")
      (node (ref "C6") (pin "2") (pinfunction "2_2") (pintype "passive"))
      (node (ref "Q1") (pin "1") (pinfunction "G_1") (pintype "passive"))
      (node (ref "Q4") (pin "1") (pinfunction "G_1") (pintype "passive"))
      (node (ref "TP9") (pin "1") (pinfunction "1_1") (pintype "passive"))
      (node (ref "U1") (pin "6") (pinfunction "GATE1_6") (pintype "input"))
    )
    (net (code "7") (name "GATE2") (class "Default")
      (node (ref "C5") (pin "2") (pinfunction "2_2") (pintype "passive"))
      (node (ref "Q2") (pin "1") (pinfunction "G_1") (pintype "passive"))
      (node (ref "Q3") (pin "1") (pinfunction "G_1") (pintype "passive"))
      (node (ref "TP2") (pin "1") (pinfunction "1_1") (pintype "passive"))
      (node (ref "U1") (pin "31") (pinfunction "GATE2_31") (pintype "input"))
    )
    (net (code "8") (name "GLVMS") (class "Default")
      (node (ref "D2") (pin "A") (pinfunction "A_A") (pintype "passive"))
      (node (ref "J2") (pin "B") (pinfunction "2_B") (pintype "passive"))
      (node (ref "R2") (pin "2") (pinfunction "2_2") (pintype "passive"))
    )
    (net (code "9") (name "GND") (class "Default")
      (node (ref "A1") (pin "3") (pinfunction "-VIN_3") (pintype "input"))
      (node (ref "A1") (pin "4") (pinfunction "-VOUT_4") (pintype "power_in"))
      (node (ref "A1") (pin "5") (pinfunction "-SENSE_5") (pintype "input"))
      (node (ref "C1") (pin "P$2") (pinfunction "MINUS_P$2") (pintype "passive"))
      (node (ref "C10") (pin "1") (pinfunction "1_1") (pintype "passive"))
      (node (ref "C100") (pin "2") (pinfunction "2_2") (pintype "passive"))
      (node (ref "C101") (pin "2") (pinfunction "2_2") (pintype "passive"))
      (node (ref "C102") (pin "2") (pinfunction "2_2") (pintype "passive"))
      (node (ref "C103") (pin "2") (pinfunction "2_2") (pintype "passive"))
      (node (ref "C104") (pin "2") (pinfunction "2_2") (pintype "passive"))
      (node (ref "C105") (pin "2") (pinfunction "2_2") (pintype "passive"))
      (node (ref "C11") (pin "2") (pinfunction "2_2") (pintype "passive"))
      (node (ref "C13") (pin "2") (pinfunction "2_2") (pintype "passive"))
      (node (ref "C2") (pin "2") (pinfunction "2_2") (pintype "passive"))
      (node (ref "C3") (pin "2") (pinfunction "2_2") (pintype "passive"))
      (node (ref "C4") (pin "2") (pinfunction "2_2") (pintype "passive"))
      (node (ref "C7") (pin "2") (pinfunction "2_2") (pintype "passive"))
      (node (ref "C8") (pin "2") (pinfunction "2_2") (pintype "passive"))
      (node (ref "C9") (pin "2") (pinfunction "2_2") (pintype "passive"))
      (node (ref "D1") (pin "1") (pinfunction "A_1") (pintype "passive"))
      (node (ref "D17") (pin "1") (pinfunction "C_1") (pintype "passive"))
      (node (ref "D4") (pin "1") (pinfunction "A_1") (pintype "passive"))
      (node (ref "D5") (pin "1") (pinfunction "A_1") (pintype "passive"))
      (node (ref "D6") (pin "1") (pinfunction "A_1") (pintype "passive"))
      (node (ref "D7") (pin "1") (pinfunction "C_1") (pintype "passive"))
      (node (ref "D8") (pin "1") (pinfunction "C_1") (pintype "passive"))
      (node (ref "D9") (pin "1") (pinfunction "C_1") (pintype "passive"))
      (node (ref "J2") (pin "A") (pinfunction "1_A") (pintype "passive"))
      (node (ref "K1") (pin "4") (pinfunction "CONTROL-_4") (pintype "passive"))
      (node (ref "R1") (pin "1") (pinfunction "1_1") (pintype "passive"))
      (node (ref "R101") (pin "1") (pinfunction "1_1") (pintype "passive"))
      (node (ref "R2") (pin "1") (pinfunction "1_1") (pintype "passive"))
      (node (ref "R23") (pin "1") (pinfunction "1_1") (pintype "passive"))
      (node (ref "R3") (pin "1") (pinfunction "1_1") (pintype "passive"))
      (node (ref "R7") (pin "1") (pinfunction "1_1") (pintype "passive"))
      (node (ref "TP6") (pin "1") (pinfunction "1_1") (pintype "passive"))
      (node (ref "U1") (pin "20") (pinfunction "RETRY_20") (pintype "input"))
      (node (ref "U1") (pin "35") (pinfunction "GND_35") (pintype "power_in"))
    )
    (net (code "10") (name "INTVDD") (class "Default")
      (node (ref "C11") (pin "1") (pinfunction "1_1") (pintype "passive"))
      (node (ref "R14") (pin "2") (pinfunction "2_2") (pintype "passive"))
      (node (ref "R16") (pin "2") (pinfunction "2_2") (pintype "passive"))
      (node (ref "R17") (pin "2") (pinfunction "2_2") (pintype "passive"))
      (node (ref "R18") (pin "2") (pinfunction "2_2") (pintype "passive"))
      (node (ref "R19") (pin "2") (pinfunction "2_2") (pintype "passive"))
      (node (ref "R20") (pin "2") (pinfunction "2_2") (pintype "passive"))
      (node (ref "R21") (pin "2") (pinfunction "2_2") (pintype "passive"))
      (node (ref "TP3") (pin "1") (pinfunction "1_1") (pintype "passive"))
      (node (ref "U1") (pin "16") (pinfunction "CASIN_16") (pintype "input"))
      (node (ref "U1") (pin "17") (pinfunction "INTVDD_17") (pintype "power_in"))
    )
    (net (code "11") (name "Net-(A1-TRIM)") (class "Default")
      (node (ref "A1") (pin "6") (pinfunction "TRIM_6") (pintype "input"))
      (node (ref "R100") (pin "1") (pinfunction "1_1") (pintype "passive"))
      (node (ref "R101") (pin "2") (pinfunction "2_2") (pintype "passive"))
    )
    (net (code "12") (name "Net-(C1-PLUS)") (class "Default")
      (node (ref "C1") (pin "P$1") (pinfunction "PLUS_P$1") (pintype "passive"))
      (node (ref "C10") (pin "2") (pinfunction "2_2") (pintype "passive"))
      (node (ref "C12") (pin "1") (pinfunction "1_1") (pintype "passive"))
      (node (ref "C2") (pin "1") (pinfunction "1_1") (pintype "passive"))
      (node (ref "C3") (pin "1") (pinfunction "1_1") (pintype "passive"))
      (node (ref "D4") (pin "3") (pinfunction "C_3") (pintype "passive"))
      (node (ref "R22") (pin "2") (pinfunction "2_2") (pintype "passive"))
      (node (ref "R4") (pin "2") (pinfunction "2_2") (pintype "passive"))
      (node (ref "R5") (pin "2") (pinfunction "2_2") (pintype "passive"))
      (node (ref "U1") (pin "2") (pinfunction "CPOREF_2") (pintype "input"))
      (node (ref "U1") (pin "36") (pinfunction "EXTVDD_36") (pintype "power_in"))
      (node (ref "XF3") (pin "1") (pinfunction "1_1") (pintype "passive"))
      (node (ref "XF3") (pin "2") (pinfunction "1_2") (pintype "passive"))
    )
    (net (code "13") (name "Net-(C4-Pad1)") (class "Default")
      (node (ref "C4") (pin "1") (pinfunction "1_1") (pintype "passive"))
      (node (ref "R6") (pin "1") (pinfunction "1_1") (pintype "passive"))
    )
    (net (code "14") (name "Net-(C7-Pad1)") (class "Default")
      (node (ref "C7") (pin "1") (pinfunction "1_1") (pintype "passive"))
      (node (ref "R8") (pin "1") (pinfunction "1_1") (pintype "passive"))
    )
    (net (code "15") (name "Net-(D6-C)") (class "Default")
      (node (ref "D6") (pin "3") (pinfunction "C_3") (pintype "passive"))
      (node (ref "Q4") (pin "2") (pinfunction "D_2") (pintype "passive"))
      (node (ref "R12") (pin "2") (pinfunction "2_2") (pintype "passive"))
      (node (ref "R26") (pin "2") (pinfunction "2_2") (pintype "passive"))
      (node (ref "R8") (pin "2") (pinfunction "2_2") (pintype "passive"))
      (node (ref "U1") (pin "7") (pinfunction "V1_7") (pintype "input"))
      (node (ref "XF4") (pin "3") (pinfunction "2_3") (pintype "passive"))
      (node (ref "XF4") (pin "4") (pinfunction "2_4") (pintype "passive"))
    )
    (net (code "16") (name "Net-(D7-A)") (class "Default")
      (node (ref "D7") (pin "2") (pinfunction "A_2") (pintype "passive"))
      (node (ref "R12") (pin "1") (pinfunction "1_1") (pintype "passive"))
    )
    (net (code "17") (name "Net-(D8-A)") (class "Default")
      (node (ref "D8") (pin "2") (pinfunction "A_2") (pintype "passive"))
      (node (ref "R13") (pin "1") (pinfunction "1_1") (pintype "passive"))
    )
    (net (code "18") (name "Net-(D9-A)") (class "Default")
      (node (ref "D9") (pin "2") (pinfunction "A_2") (pintype "passive"))
      (node (ref "R14") (pin "1") (pinfunction "1_1") (pintype "passive"))
    )
    (net (code "19") (name "Net-(D10-A)") (class "Default")
      (node (ref "D10") (pin "2") (pinfunction "A_2") (pintype "passive"))
      (node (ref "R15") (pin "1") (pinfunction "1_1") (pintype "passive"))
    )
    (net (code "20") (name "Net-(D11-A)") (class "Default")
      (node (ref "D11") (pin "2") (pinfunction "A_2") (pintype "passive"))
      (node (ref "R16") (pin "1") (pinfunction "1_1") (pintype "passive"))
    )
    (net (code "21") (name "Net-(D11-C)") (class "Default")
      (node (ref "D11") (pin "1") (pinfunction "C_1") (pintype "passive"))
      (node (ref "U1") (pin "14") (pinfunction "~{VALID1}_14") (pintype "open_collector"))
    )
    (net (code "22") (name "Net-(D12-A)") (class "Default")
      (node (ref "D12") (pin "2") (pinfunction "A_2") (pintype "passive"))
      (node (ref "R17") (pin "1") (pinfunction "1_1") (pintype "passive"))
    )
    (net (code "23") (name "Net-(D12-C)") (class "Default")
      (node (ref "D12") (pin "1") (pinfunction "C_1") (pintype "passive"))
      (node (ref "U1") (pin "23") (pinfunction "~{VALID2}_23") (pintype "open_collector"))
    )
    (net (code "24") (name "Net-(D13-A)") (class "Default")
      (node (ref "D13") (pin "2") (pinfunction "A_2") (pintype "passive"))
      (node (ref "R18") (pin "1") (pinfunction "1_1") (pintype "passive"))
    )
    (net (code "25") (name "Net-(D13-C)") (class "Default")
      (node (ref "D13") (pin "1") (pinfunction "C_1") (pintype "passive"))
      (node (ref "U1") (pin "13") (pinfunction "~{CH1}_13") (pintype "open_collector"))
    )
    (net (code "26") (name "Net-(D14-A)") (class "Default")
      (node (ref "D14") (pin "2") (pinfunction "A_2") (pintype "passive"))
      (node (ref "R19") (pin "1") (pinfunction "1_1") (pintype "passive"))
    )
    (net (code "27") (name "Net-(D14-C)") (class "Default")
      (node (ref "D14") (pin "1") (pinfunction "C_1") (pintype "passive"))
      (node (ref "U1") (pin "24") (pinfunction "~{CH2}_24") (pintype "open_collector"))
    )
    (net (code "28") (name "Net-(D15-A)") (class "Default")
      (node (ref "D15") (pin "2") (pinfunction "A_2") (pintype "passive"))
      (node (ref "R20") (pin "1") (pinfunction "1_1") (pintype "passive"))
    )
    (net (code "29") (name "Net-(D15-C)") (class "Default")
      (node (ref "D15") (pin "1") (pinfunction "C_1") (pintype "passive"))
      (node (ref "U1") (pin "15") (pinfunction "~{FAULT1}_15") (pintype "open_collector"))
    )
    (net (code "30") (name "Net-(D16-A)") (class "Default")
      (node (ref "D16") (pin "2") (pinfunction "A_2") (pintype "passive"))
      (node (ref "R21") (pin "1") (pinfunction "1_1") (pintype "passive"))
    )
    (net (code "31") (name "Net-(D16-C)") (class "Default")
      (node (ref "D16") (pin "1") (pinfunction "C_1") (pintype "passive"))
      (node (ref "U1") (pin "22") (pinfunction "~{FAULT2}_22") (pintype "open_collector"))
    )
    (net (code "32") (name "Net-(D17-A)") (class "Default")
      (node (ref "D17") (pin "2") (pinfunction "A_2") (pintype "passive"))
      (node (ref "R22") (pin "1") (pinfunction "1_1") (pintype "passive"))
    )
    (net (code "33") (name "Net-(K1-CONTACT1)") (class "Default")
      (node (ref "K1") (pin "1") (pinfunction "CONTACT1_1") (pintype "bidirectional"))
      (node (ref "XF1") (pin "1") (pinfunction "1_1") (pintype "passive"))
      (node (ref "XF1") (pin "2") (pinfunction "1_2") (pintype "passive"))
    )
    (net (code "34") (name "Net-(Q1-D)") (class "Default")
      (node (ref "Q1") (pin "2") (pinfunction "D_2") (pintype "passive"))
      (node (ref "R4") (pin "1") (pinfunction "1_1") (pintype "passive"))
    )
    (net (code "35") (name "Net-(Q2-D)") (class "Default")
      (node (ref "Q2") (pin "2") (pinfunction "D_2") (pintype "passive"))
      (node (ref "R5") (pin "1") (pinfunction "1_1") (pintype "passive"))
    )
    (net (code "36") (name "Net-(U1-OUT1)") (class "Default")
      (node (ref "R4") (pin "4") (pinfunction "4_4") (pintype "passive"))
      (node (ref "U1") (pin "3") (pinfunction "OUT1_3") (pintype "input"))
    )
    (net (code "37") (name "Net-(U1-OUT2)") (class "Default")
      (node (ref "R5") (pin "4") (pinfunction "4_4") (pintype "passive"))
      (node (ref "U1") (pin "34") (pinfunction "OUT2_34") (pintype "input"))
    )
    (net (code "38") (name "Net-(U1-OV1)") (class "Default")
      (node (ref "R23") (pin "2") (pinfunction "2_2") (pintype "passive"))
      (node (ref "R24") (pin "1") (pinfunction "1_1") (pintype "passive"))
      (node (ref "U1") (pin "10") (pinfunction "OV1_10") (pintype "input"))
    )
    (net (code "39") (name "Net-(U1-OV2)") (class "Default")
      (node (ref "R7") (pin "2") (pinfunction "2_2") (pintype "passive"))
      (node (ref "R9") (pin "1") (pinfunction "1_1") (pintype "passive"))
      (node (ref "U1") (pin "27") (pinfunction "OV2_27") (pintype "input"))
    )
    (net (code "40") (name "Net-(U1-QUAL)") (class "Default")
      (node (ref "C9") (pin "1") (pinfunction "1_1") (pintype "passive"))
      (node (ref "U1") (pin "19") (pinfunction "QUAL_19") (pintype "bidirectional"))
    )
    (net (code "41") (name "Net-(U1-SENSE1)") (class "Default")
      (node (ref "R4") (pin "3") (pinfunction "3_3") (pintype "passive"))
      (node (ref "U1") (pin "4") (pinfunction "SENSE1_4") (pintype "input"))
    )
    (net (code "42") (name "Net-(U1-SENSE2)") (class "Default")
      (node (ref "R5") (pin "3") (pinfunction "3_3") (pintype "passive"))
      (node (ref "U1") (pin "33") (pinfunction "SENSE2_33") (pintype "input"))
    )
    (net (code "43") (name "Net-(U1-TMR1)") (class "Default")
      (node (ref "C13") (pin "1") (pinfunction "1_1") (pintype "passive"))
      (node (ref "U1") (pin "11") (pinfunction "TMR1_11") (pintype "bidirectional"))
    )
    (net (code "44") (name "Net-(U1-TMR2)") (class "Default")
      (node (ref "C8") (pin "1") (pinfunction "1_1") (pintype "passive"))
      (node (ref "U1") (pin "26") (pinfunction "TMR2_26") (pintype "bidirectional"))
    )
    (net (code "45") (name "Net-(U1-UVF1)") (class "Default")
      (node (ref "R25") (pin "2") (pinfunction "2_2") (pintype "passive"))
      (node (ref "R26") (pin "1") (pinfunction "1_1") (pintype "passive"))
      (node (ref "U1") (pin "8") (pinfunction "UVF1_8") (pintype "input"))
    )
    (net (code "46") (name "Net-(U1-UVF2)") (class "Default")
      (node (ref "R10") (pin "2") (pinfunction "2_2") (pintype "passive"))
      (node (ref "R11") (pin "1") (pinfunction "1_1") (pintype "passive"))
      (node (ref "U1") (pin "29") (pinfunction "UVF2_29") (pintype "input"))
    )
    (net (code "47") (name "Net-(U1-UVR1)") (class "Default")
      (node (ref "R24") (pin "2") (pinfunction "2_2") (pintype "passive"))
      (node (ref "R25") (pin "1") (pinfunction "1_1") (pintype "passive"))
      (node (ref "U1") (pin "9") (pinfunction "UVR1_9") (pintype "input"))
    )
    (net (code "48") (name "Net-(U1-UVR2)") (class "Default")
      (node (ref "R10") (pin "1") (pinfunction "1_1") (pintype "passive"))
      (node (ref "R9") (pin "2") (pinfunction "2_2") (pintype "passive"))
      (node (ref "U1") (pin "28") (pinfunction "UVR2_28") (pintype "input"))
    )
    (net (code "49") (name "OUT") (class "Default")
      (node (ref "J1") (pin "3") (pinfunction "3_3") (pintype "passive"))
      (node (ref "J1") (pin "4") (pinfunction "4_4") (pintype "passive"))
      (node (ref "TP7") (pin "1") (pinfunction "1_1") (pintype "passive"))
      (node (ref "XF2") (pin "3") (pinfunction "2_3") (pintype "passive"))
      (node (ref "XF2") (pin "4") (pinfunction "2_4") (pintype "passive"))
      (node (ref "XF3") (pin "3") (pinfunction "2_3") (pintype "passive"))
      (node (ref "XF3") (pin "4") (pinfunction "2_4") (pintype "passive"))
    )
    (net (code "50") (name "SHDNLINE") (class "Default")
      (node (ref "A1") (pin "2") (pinfunction "ON/OFF_2") (pintype "input"))
      (node (ref "K1") (pin "3") (pinfunction "CONTROL+_3") (pintype "passive"))
      (node (ref "R15") (pin "2") (pinfunction "2_2") (pintype "passive"))
    )
    (net (code "51") (name "SOURCE1") (class "Default")
      (node (ref "C6") (pin "1") (pinfunction "1_1") (pintype "passive"))
      (node (ref "Q1") (pin "3") (pinfunction "S_3") (pintype "passive"))
      (node (ref "Q4") (pin "3") (pinfunction "S_3") (pintype "passive"))
      (node (ref "TP10") (pin "1") (pinfunction "1_1") (pintype "passive"))
      (node (ref "U1") (pin "5") (pinfunction "SOURCE1_5") (pintype "input"))
    )
    (net (code "52") (name "SOURCE2") (class "Default")
      (node (ref "C5") (pin "1") (pinfunction "1_1") (pintype "passive"))
      (node (ref "Q2") (pin "3") (pinfunction "S_3") (pintype "passive"))
      (node (ref "Q3") (pin "3") (pinfunction "S_3") (pintype "passive"))
      (node (ref "TP5") (pin "1") (pinfunction "1_1") (pintype "passive"))
      (node (ref "U1") (pin "32") (pinfunction "SOURCE2_32") (pintype "input"))
    )
    (net (code "53") (name "START") (class "Default")
      (node (ref "D3") (pin "A") (pinfunction "A_A") (pintype "passive"))
      (node (ref "J2") (pin "C") (pinfunction "3_C") (pintype "passive"))
      (node (ref "R1") (pin "2") (pinfunction "2_2") (pintype "passive"))
    )
    (net (code "54") (name "unconnected-(J3-Pad3)") (class "Default")
      (node (ref "J3") (pin "3") (pinfunction "3_3") (pintype "passive"))
    )
    (net (code "55") (name "unconnected-(J3-Pad4)") (class "Default")
      (node (ref "J3") (pin "4") (pinfunction "4_4") (pintype "passive"))
    )
    (net (code "56") (name "unconnected-(U1-CASOUT-Pad18)") (class "Default")
      (node (ref "U1") (pin "18") (pinfunction "CASOUT_18") (pintype "output"))
    )
    (net (code "57") (name "~{SHDN}") (class "Default")
      (node (ref "D10") (pin "1") (pinfunction "C_1") (pintype "passive"))
      (node (ref "D2") (pin "C") (pinfunction "C_C") (pintype "passive"))
      (node (ref "D3") (pin "C") (pinfunction "C_C") (pintype "passive"))
      (node (ref "R3") (pin "2") (pinfunction "2_2") (pintype "passive"))
      (node (ref "TP11") (pin "1") (pinfunction "1_1") (pintype "passive"))
      (node (ref "U1") (pin "12") (pinfunction "~{DISABLE1}_12") (pintype "input"))
      (node (ref "U1") (pin "21") (pinfunction "~{SHDN}_21") (pintype "input"))
      (node (ref "U1") (pin "25") (pinfunction "~{DISABLE2}_25") (pintype "input"))
    )
  )
)
